# pk2.net
KiCad netlist of a schematic drawn in Altium Designer
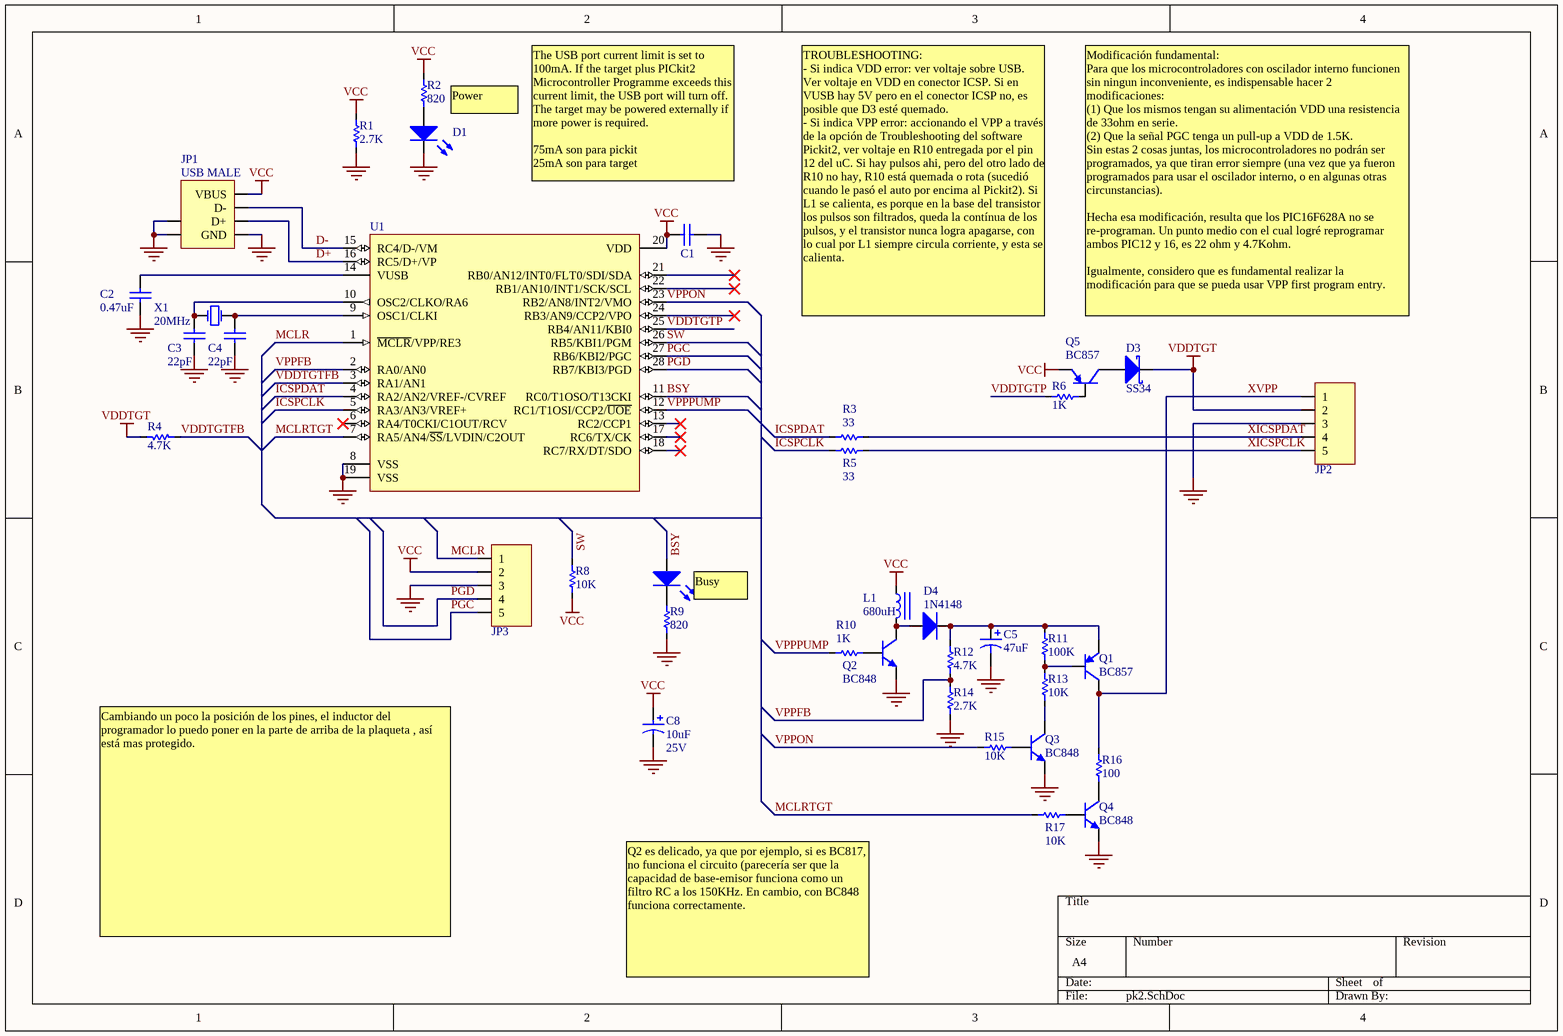
[diagram p0: pk2.SchDoc]

(export (version "E")
  (design (tool "Eeschema 10.0.6"))
  (components
    (comp (ref "C1")
      (value "Cap")
      (footprint "1206NP")
      (description "Capacitor")
      (fields (field (name "VOLTAGE") "50V"))
      (libsource (lib "FEDE") (part "Cap"))
    )
    (comp (ref "C2")
      (value "0.47uF")
      (footprint "1206NP")
      (description "Capacitor")
      (fields (field (name "VOLTAGE") "50V") (field (name "Comment") "Cap"))
      (libsource (lib "FEDE") (part "Cap"))
    )
    (comp (ref "C3")
      (value "22pF")
      (footprint "1206NP")
      (description "Capacitor")
      (fields (field (name "VOLTAGE") "50V") (field (name "Comment") "Cap"))
      (libsource (lib "FEDE") (part "Cap"))
    )
    (comp (ref "C4")
      (value "22pF")
      (footprint "1206NP")
      (description "Capacitor")
      (fields (field (name "VOLTAGE") "50V") (field (name "Comment") "Cap"))
      (libsource (lib "FEDE") (part "Cap"))
    )
    (comp (ref "C5")
      (value "47uF")
      (footprint "D")
      (description "Solid Tantalum Chip Capacitor, Standard T491 Series - Industrial Grade")
      (fields (field (name "PUBLISHER") "Altium Limited"))
      (libsource (lib "KEMET Chip Capacitor") (part "T491D"))
    )
    (comp (ref "C8")
      (value "10uF")
      (footprint "1206P")
      (description "Capacitor Polarizado")
      (fields (field (name "VOLTAJE") "25V") (field (name "Comment") "Cap Pol"))
      (libsource (lib "FEDE") (part "Cap Pol"))
    )
    (comp (ref "D1")
      (value "LED")
      (footprint "1206P")
      (description "Led")
      (libsource (lib "FEDE") (part "LED"))
    )
    (comp (ref "D2")
      (value "LED")
      (footprint "1206P")
      (description "Led")
      (libsource (lib "FEDE") (part "LED"))
    )
    (comp (ref "D3")
      (value "SS34")
      (footprint "D64")
      (description "Schottky Diode 3A 40V")
      (libsource (lib "FEDE") (part "1N5822"))
    )
    (comp (ref "D4")
      (value "1N4148")
      (footprint "DSMD1MM")
      (description "High Conductance Fast Diode")
      (libsource (lib "FEDE") (part "1N4148"))
    )
    (comp (ref "JP1")
      (value "USB MALE")
      (footprint "USB_A_MALE")
      (description "USB Connector")
      (libsource (lib "FEDE") (part "USB"))
    )
    (comp (ref "JP2")
      (value "Header5x1")
      (footprint "HDR5x1")
      (description "Header 5x1")
      (libsource (lib "FEDE") (part "Header5x1"))
    )
    (comp (ref "JP3")
      (value "Header5x1")
      (footprint "HDR5x1")
      (description "Header 5x1")
      (libsource (lib "FEDE") (part "Header5x1"))
    )
    (comp (ref "L1")
      (value "680uH")
      (footprint "RES300TH")
      (description "Inductor")
      (libsource (lib "FEDE") (part "Inductor"))
    )
    (comp (ref "Q1")
      (value "BC857")
      (footprint "SOT23")
      (description "100mA 65V PNP Bipolar Transistor")
      (libsource (lib "FEDE") (part "BC856A"))
    )
    (comp (ref "Q2")
      (value "BC848")
      (footprint "SOT23")
      (description "100mA 65V NPN Bipolar Transistor")
      (libsource (lib "FEDE") (part "BC846A"))
    )
    (comp (ref "Q3")
      (value "BC848")
      (footprint "SOT23")
      (description "100mA 65V NPN Bipolar Transistor")
      (libsource (lib "FEDE") (part "BC846A"))
    )
    (comp (ref "Q4")
      (value "BC848")
      (footprint "SOT23")
      (description "100mA 65V NPN Bipolar Transistor")
      (libsource (lib "FEDE") (part "BC846A"))
    )
    (comp (ref "Q5")
      (value "BC857")
      (footprint "SOT23")
      (description "100mA 65V PNP Bipolar Transistor")
      (libsource (lib "FEDE") (part "BC856A"))
    )
    (comp (ref "R1")
      (value "2.7K")
      (footprint "1206NP")
      (description "Resistor")
      (fields (field (name "POWER") "0.25W") (field (name "Comment") "Res"))
      (libsource (lib "FEDE") (part "Res"))
    )
    (comp (ref "R2")
      (value "820")
      (footprint "1206NP")
      (description "Resistor")
      (fields (field (name "POWER") "0.25W") (field (name "Comment") "Res"))
      (libsource (lib "FEDE") (part "Res"))
    )
    (comp (ref "R3")
      (value "33")
      (footprint "1206NP")
      (description "Resistor")
      (fields (field (name "POWER") "0.25W") (field (name "Comment") "Res"))
      (libsource (lib "FEDE") (part "Res"))
    )
    (comp (ref "R4")
      (value "4.7K")
      (footprint "1206NP")
      (description "Resistor")
      (fields (field (name "POWER") "0.25W") (field (name "Comment") "Res"))
      (libsource (lib "FEDE") (part "Res"))
    )
    (comp (ref "R5")
      (value "33")
      (footprint "1206NP")
      (description "Resistor")
      (fields (field (name "POWER") "0.25W") (field (name "Comment") "Res"))
      (libsource (lib "FEDE") (part "Res"))
    )
    (comp (ref "R6")
      (value "1K")
      (footprint "1206NP")
      (description "Resistor")
      (fields (field (name "POWER") "0.25W") (field (name "Comment") "Res"))
      (libsource (lib "FEDE") (part "Res"))
    )
    (comp (ref "R8")
      (value "10K")
      (footprint "1206NP")
      (description "Resistor")
      (fields (field (name "POWER") "0.25W") (field (name "Comment") "Res"))
      (libsource (lib "FEDE") (part "Res"))
    )
    (comp (ref "R9")
      (value "820")
      (footprint "1206NP")
      (description "Resistor")
      (fields (field (name "POWER") "0.25W") (field (name "Comment") "Res"))
      (libsource (lib "FEDE") (part "Res"))
    )
    (comp (ref "R10")
      (value "1K")
      (footprint "1206NP")
      (description "Resistor")
      (fields (field (name "POWER") "0.25W") (field (name "Comment") "Res"))
      (libsource (lib "FEDE") (part "Res"))
    )
    (comp (ref "R11")
      (value "100K")
      (footprint "1206NP")
      (description "Resistor")
      (fields (field (name "POWER") "0.25W") (field (name "Comment") "Res"))
      (libsource (lib "FEDE") (part "Res"))
    )
    (comp (ref "R12")
      (value "4.7K")
      (footprint "1206NP")
      (description "Resistor")
      (fields (field (name "POWER") "0.25W") (field (name "Comment") "Res"))
      (libsource (lib "FEDE") (part "Res"))
    )
    (comp (ref "R13")
      (value "10K")
      (footprint "1206NP")
      (description "Resistor")
      (fields (field (name "POWER") "0.25W") (field (name "Comment") "Res"))
      (libsource (lib "FEDE") (part "Res"))
    )
    (comp (ref "R14")
      (value "2.7K")
      (footprint "1206NP")
      (description "Resistor")
      (fields (field (name "POWER") "0.25W") (field (name "Comment") "Res"))
      (libsource (lib "FEDE") (part "Res"))
    )
    (comp (ref "R15")
      (value "10K")
      (footprint "1206NP")
      (description "Resistor")
      (fields (field (name "POWER") "0.25W") (field (name "Comment") "Res"))
      (libsource (lib "FEDE") (part "Res"))
    )
    (comp (ref "R16")
      (value "100")
      (footprint "1206NP")
      (description "Resistor")
      (fields (field (name "POWER") "0.25W") (field (name "Comment") "Res"))
      (libsource (lib "FEDE") (part "Res"))
    )
    (comp (ref "R17")
      (value "10K")
      (footprint "1206NP")
      (description "Resistor")
      (fields (field (name "POWER") "0.25W") (field (name "Comment") "Res"))
      (libsource (lib "FEDE") (part "Res"))
    )
    (comp (ref "U1")
      (value "~")
      (footprint "soic28")
      (description "Enhanced FLASH Microcontroller")
      (libsource (lib "FEDE") (part "PIC18F2550"))
    )
    (comp (ref "X1")
      (value "20MHz")
      (footprint "XTAL1")
      (description "Crystal Oscillator")
      (fields (field (name "Comment") "XTAL"))
      (libsource (lib "FEDE") (part "XTAL"))
    )
  )
  (nets
    (net (code "1") (name "/BSY") (class "Default")
      (node (ref "D2") (pin "1") (pinfunction "A_1") (pintype "passive"))
      (node (ref "U1") (pin "11") (pinfunction "RC0/T1OSO/T13CKI_11") (pintype "bidirectional"))
    )
    (net (code "2") (name "/D+") (class "Default")
      (node (ref "JP1") (pin "3") (pinfunction "D+_3") (pintype "passive"))
      (node (ref "U1") (pin "16") (pinfunction "RC5/D+/VP_16") (pintype "bidirectional"))
    )
    (net (code "3") (name "/D-") (class "Default")
      (node (ref "JP1") (pin "2") (pinfunction "D-_2") (pintype "passive"))
      (node (ref "U1") (pin "15") (pinfunction "RC4/D-/VM_15") (pintype "bidirectional"))
    )
    (net (code "4") (name "/ICSPCLK") (class "Default")
      (node (ref "R5") (pin "1") (pinfunction "1_1") (pintype "passive"))
      (node (ref "U1") (pin "5") (pinfunction "RA3/AN3/VREF+_5") (pintype "bidirectional"))
    )
    (net (code "5") (name "/ICSPDAT") (class "Default")
      (node (ref "R3") (pin "1") (pinfunction "1_1") (pintype "passive"))
      (node (ref "U1") (pin "4") (pinfunction "RA2/AN2/VREF-/CVREF_4") (pintype "bidirectional"))
    )
    (net (code "6") (name "/MCLR") (class "Default")
      (node (ref "JP3") (pin "1") (pinfunction "1_1") (pintype "passive"))
      (node (ref "U1") (pin "1") (pinfunction "~{MCLR}/VPP/RE3_1") (pintype "input"))
    )
    (net (code "7") (name "/MCLRTGT") (class "Default")
      (node (ref "R17") (pin "2") (pinfunction "2_2") (pintype "passive"))
      (node (ref "U1") (pin "7") (pinfunction "RA5/AN4/~{SS}/LVDIN/C2OUT_7") (pintype "bidirectional"))
    )
    (net (code "8") (name "/PGC") (class "Default")
      (node (ref "JP3") (pin "5") (pinfunction "5_5") (pintype "passive"))
      (node (ref "U1") (pin "27") (pinfunction "RB6/KBI2/PGC_27") (pintype "bidirectional"))
    )
    (net (code "9") (name "/PGD") (class "Default")
      (node (ref "JP3") (pin "4") (pinfunction "4_4") (pintype "passive"))
      (node (ref "U1") (pin "28") (pinfunction "RB7/KBI3/PGD_28") (pintype "bidirectional"))
    )
    (net (code "10") (name "/SW") (class "Default")
      (node (ref "R8") (pin "1") (pinfunction "1_1") (pintype "passive"))
      (node (ref "U1") (pin "26") (pinfunction "RB5/KBI1/PGM_26") (pintype "bidirectional"))
    )
    (net (code "11") (name "/VDDTGTFB") (class "Default")
      (node (ref "R4") (pin "1") (pinfunction "1_1") (pintype "passive"))
      (node (ref "U1") (pin "3") (pinfunction "RA1/AN1_3") (pintype "bidirectional"))
    )
    (net (code "12") (name "/VDDTGTP") (class "Default")
      (node (ref "R6") (pin "2") (pinfunction "2_2") (pintype "passive"))
      (node (ref "U1") (pin "25") (pinfunction "RB4/AN11/KBI0_25") (pintype "bidirectional"))
    )
    (net (code "13") (name "/VPPFB") (class "Default")
      (node (ref "R12") (pin "1") (pinfunction "1_1") (pintype "passive"))
      (node (ref "R14") (pin "2") (pinfunction "2_2") (pintype "passive"))
      (node (ref "U1") (pin "2") (pinfunction "RA0/AN0_2") (pintype "bidirectional"))
    )
    (net (code "14") (name "/VPPON") (class "Default")
      (node (ref "R15") (pin "2") (pinfunction "2_2") (pintype "passive"))
      (node (ref "U1") (pin "23") (pinfunction "RB2/AN8/INT2/VMO_23") (pintype "bidirectional"))
    )
    (net (code "15") (name "/VPPPUMP") (class "Default")
      (node (ref "R10") (pin "2") (pinfunction "2_2") (pintype "passive"))
      (node (ref "U1") (pin "12") (pinfunction "RC1/T1OSI/CCP2/~{UOE}_12") (pintype "bidirectional"))
    )
    (net (code "16") (name "/XICSPCLK") (class "Default")
      (node (ref "JP2") (pin "5") (pinfunction "5_5") (pintype "passive"))
      (node (ref "R5") (pin "2") (pinfunction "2_2") (pintype "passive"))
    )
    (net (code "17") (name "/XICSPDAT") (class "Default")
      (node (ref "JP2") (pin "4") (pinfunction "4_4") (pintype "passive"))
      (node (ref "R3") (pin "2") (pinfunction "2_2") (pintype "passive"))
    )
    (net (code "18") (name "/XVPP") (class "Default")
      (node (ref "JP2") (pin "1") (pinfunction "1_1") (pintype "passive"))
      (node (ref "Q1") (pin "1") (pinfunction "C_1") (pintype "passive"))
      (node (ref "R16") (pin "2") (pinfunction "2_2") (pintype "passive"))
    )
    (net (code "19") (name "GND") (class "Default")
      (node (ref "C1") (pin "1") (pinfunction "1_1") (pintype "passive"))
      (node (ref "C2") (pin "1") (pinfunction "1_1") (pintype "passive"))
      (node (ref "C3") (pin "1") (pinfunction "1_1") (pintype "passive"))
      (node (ref "C4") (pin "2") (pinfunction "2_2") (pintype "passive"))
      (node (ref "C5") (pin "2") (pinfunction "2_2") (pintype "passive"))
      (node (ref "C8") (pin "2") (pinfunction "2_2") (pintype "passive"))
      (node (ref "D1") (pin "2") (pinfunction "K_2") (pintype "passive"))
      (node (ref "JP1") (pin "4") (pinfunction "GND_4") (pintype "passive"))
      (node (ref "JP1") (pin "5") (pintype "passive"))
      (node (ref "JP1") (pin "6") (pintype "passive"))
      (node (ref "JP2") (pin "3") (pinfunction "3_3") (pintype "passive"))
      (node (ref "JP3") (pin "3") (pinfunction "3_3") (pintype "passive"))
      (node (ref "Q2") (pin "3") (pinfunction "E_3") (pintype "passive"))
      (node (ref "Q3") (pin "3") (pinfunction "E_3") (pintype "passive"))
      (node (ref "Q4") (pin "3") (pinfunction "E_3") (pintype "passive"))
      (node (ref "R1") (pin "2") (pinfunction "2_2") (pintype "passive"))
      (node (ref "R14") (pin "1") (pinfunction "1_1") (pintype "passive"))
      (node (ref "R9") (pin "1") (pinfunction "1_1") (pintype "passive"))
      (node (ref "U1") (pin "19") (pinfunction "VSS_19") (pintype "power_in"))
      (node (ref "U1") (pin "8") (pinfunction "VSS_8") (pintype "power_in"))
    )
    (net (code "20") (name "Net-(D1-A)") (class "Default")
      (node (ref "D1") (pin "1") (pinfunction "A_1") (pintype "passive"))
      (node (ref "R2") (pin "1") (pinfunction "1_1") (pintype "passive"))
    )
    (net (code "21") (name "Net-(D2-K)") (class "Default")
      (node (ref "D2") (pin "2") (pinfunction "K_2") (pintype "passive"))
      (node (ref "R9") (pin "2") (pinfunction "2_2") (pintype "passive"))
    )
    (net (code "22") (name "Net-(D3-A)") (class "Default")
      (node (ref "D3") (pin "1") (pinfunction "A_1") (pintype "passive"))
      (node (ref "Q5") (pin "1") (pinfunction "C_1") (pintype "passive"))
    )
    (net (code "23") (name "Net-(Q1-B)") (class "Default")
      (node (ref "Q1") (pin "2") (pinfunction "B_2") (pintype "passive"))
      (node (ref "R11") (pin "1") (pinfunction "1_1") (pintype "passive"))
      (node (ref "R13") (pin "2") (pinfunction "2_2") (pintype "passive"))
    )
    (net (code "24") (name "Net-(Q1-E)") (class "Default")
      (node (ref "C5") (pin "1") (pinfunction "1_1") (pintype "passive"))
      (node (ref "D4") (pin "2") (pinfunction "2_2") (pintype "passive"))
      (node (ref "Q1") (pin "3") (pinfunction "E_3") (pintype "passive"))
      (node (ref "R11") (pin "2") (pinfunction "2_2") (pintype "passive"))
      (node (ref "R12") (pin "2") (pinfunction "2_2") (pintype "passive"))
    )
    (net (code "25") (name "Net-(Q2-B)") (class "Default")
      (node (ref "Q2") (pin "2") (pinfunction "B_2") (pintype "passive"))
      (node (ref "R10") (pin "1") (pinfunction "1_1") (pintype "passive"))
    )
    (net (code "26") (name "Net-(Q2-C)") (class "Default")
      (node (ref "D4") (pin "1") (pinfunction "1_1") (pintype "passive"))
      (node (ref "L1") (pin "2") (pinfunction "2_2") (pintype "passive"))
      (node (ref "Q2") (pin "1") (pinfunction "C_1") (pintype "passive"))
    )
    (net (code "27") (name "Net-(Q3-B)") (class "Default")
      (node (ref "Q3") (pin "2") (pinfunction "B_2") (pintype "passive"))
      (node (ref "R15") (pin "1") (pinfunction "1_1") (pintype "passive"))
    )
    (net (code "28") (name "Net-(Q3-C)") (class "Default")
      (node (ref "Q3") (pin "1") (pinfunction "C_1") (pintype "passive"))
      (node (ref "R13") (pin "1") (pinfunction "1_1") (pintype "passive"))
    )
    (net (code "29") (name "Net-(Q4-B)") (class "Default")
      (node (ref "Q4") (pin "2") (pinfunction "B_2") (pintype "passive"))
      (node (ref "R17") (pin "1") (pinfunction "1_1") (pintype "passive"))
    )
    (net (code "30") (name "Net-(Q4-C)") (class "Default")
      (node (ref "Q4") (pin "1") (pinfunction "C_1") (pintype "passive"))
      (node (ref "R16") (pin "1") (pinfunction "1_1") (pintype "passive"))
    )
    (net (code "31") (name "Net-(Q5-B)") (class "Default")
      (node (ref "Q5") (pin "2") (pinfunction "B_2") (pintype "passive"))
      (node (ref "R6") (pin "1") (pinfunction "1_1") (pintype "passive"))
    )
    (net (code "32") (name "Net-(U1-OSC1{slash}CLKI)") (class "Default")
      (node (ref "C4") (pin "1") (pinfunction "1_1") (pintype "passive"))
      (node (ref "U1") (pin "9") (pinfunction "OSC1/CLKI_9") (pintype "input"))
      (node (ref "X1") (pin "2") (pinfunction "OSC2_2") (pintype "passive"))
    )
    (net (code "33") (name "Net-(U1-OSC2{slash}CLKO{slash}RA6)") (class "Default")
      (node (ref "C3") (pin "2") (pinfunction "2_2") (pintype "passive"))
      (node (ref "U1") (pin "10") (pinfunction "OSC2/CLKO/RA6_10") (pintype "output"))
      (node (ref "X1") (pin "1") (pinfunction "OSC1_1") (pintype "passive"))
    )
    (net (code "34") (name "Net-(U1-VUSB)") (class "Default")
      (node (ref "C2") (pin "2") (pinfunction "2_2") (pintype "passive"))
      (node (ref "U1") (pin "14") (pinfunction "VUSB_14") (pintype "passive"))
    )
    (net (code "35") (name "VCC") (class "Default")
      (node (ref "C1") (pin "2") (pinfunction "2_2") (pintype "passive"))
      (node (ref "C8") (pin "1") (pinfunction "1_1") (pintype "passive"))
      (node (ref "JP1") (pin "1") (pinfunction "VBUS_1") (pintype "passive"))
      (node (ref "JP3") (pin "2") (pinfunction "2_2") (pintype "passive"))
      (node (ref "L1") (pin "1") (pinfunction "1_1") (pintype "passive"))
      (node (ref "Q5") (pin "3") (pinfunction "E_3") (pintype "passive"))
      (node (ref "R1") (pin "1") (pinfunction "1_1") (pintype "passive"))
      (node (ref "R2") (pin "2") (pinfunction "2_2") (pintype "passive"))
      (node (ref "R8") (pin "2") (pinfunction "2_2") (pintype "passive"))
      (node (ref "U1") (pin "20") (pinfunction "VDD_20") (pintype "power_in"))
    )
    (net (code "36") (name "VDDTGT") (class "Default")
      (node (ref "D3") (pin "2") (pinfunction "K_2") (pintype "passive"))
      (node (ref "JP2") (pin "2") (pinfunction "2_2") (pintype "passive"))
      (node (ref "R4") (pin "2") (pinfunction "2_2") (pintype "passive"))
    )
    (net (code "37") (name "unconnected-(U1-RA4{slash}T0CKI{slash}C1OUT{slash}RCV-Pad6)") (class "Default")
      (node (ref "U1") (pin "6") (pinfunction "RA4/T0CKI/C1OUT/RCV_6") (pintype "bidirectional+no_connect"))
    )
    (net (code "38") (name "unconnected-(U1-RB0{slash}AN12{slash}INT0{slash}FLT0{slash}SDI{slash}SDA-Pad21)") (class "Default")
      (node (ref "U1") (pin "21") (pinfunction "RB0/AN12/INT0/FLT0/SDI/SDA_21") (pintype "bidirectional+no_connect"))
    )
    (net (code "39") (name "unconnected-(U1-RB1{slash}AN10{slash}INT1{slash}SCK{slash}SCL-Pad22)") (class "Default")
      (node (ref "U1") (pin "22") (pinfunction "RB1/AN10/INT1/SCK/SCL_22") (pintype "bidirectional+no_connect"))
    )
    (net (code "40") (name "unconnected-(U1-RB3{slash}AN9{slash}CCP2{slash}VPO-Pad24)") (class "Default")
      (node (ref "U1") (pin "24") (pinfunction "RB3/AN9/CCP2/VPO_24") (pintype "bidirectional+no_connect"))
    )
    (net (code "41") (name "unconnected-(U1-RC2{slash}CCP1-Pad13)") (class "Default")
      (node (ref "U1") (pin "13") (pinfunction "RC2/CCP1_13") (pintype "bidirectional+no_connect"))
    )
    (net (code "42") (name "unconnected-(U1-RC6{slash}TX{slash}CK-Pad17)") (class "Default")
      (node (ref "U1") (pin "17") (pinfunction "RC6/TX/CK_17") (pintype "bidirectional+no_connect"))
    )
    (net (code "43") (name "unconnected-(U1-RC7{slash}RX{slash}DT{slash}SDO-Pad18)") (class "Default")
      (node (ref "U1") (pin "18") (pinfunction "RC7/RX/DT/SDO_18") (pintype "bidirectional+no_connect"))
    )
  )
)
